# 07-TCXO_Crystal.net
KiCad netlist of a schematic drawn in Altium Designer
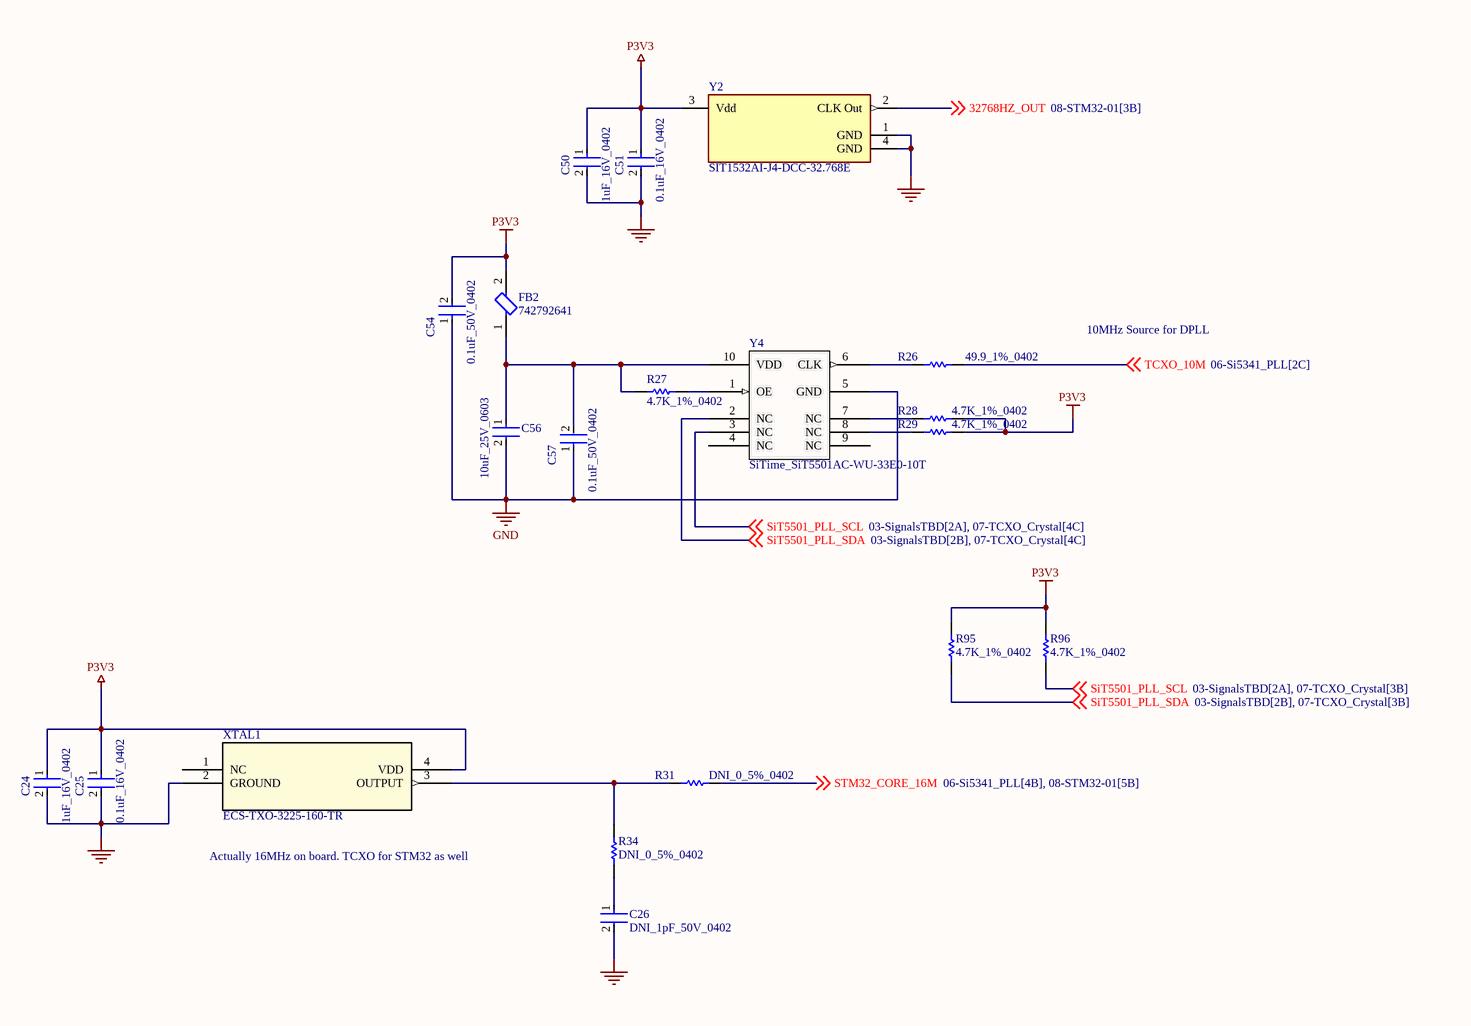
[diagram p0: 07-TCXO_Crystal.SchDoc]

(export (version "E")
  (design (tool "Eeschema 10.0.6"))
  (components
    (comp (ref "C24")
      (value "1uF_16V_0402")
      (footprint "FP-0402-L_1_0_0_05-W_0_5-IPC_A")
      (description "None")
      (fields (field (name "TOLERANCE") "10%"))
      (libsource (lib "Altium Content Vault") (part "b4654b650e69147ec39a6b967a45e02"))
    )
    (comp (ref "C25")
      (value "0.1uF_16V_0402")
      (footprint "FP-C0402-BB-MFG")
      (description "CAP CER 0.1UF 16V 5% X7R 0402")
      (fields
        (field (name "MANUFACTURER") "Kemet")
        (field (name "MANUFACTURER PART NUMBER") "C0402C104J4RACTU")
      )
      (libsource (lib "Altium Content Vault") (part "b4654b650e69147ec39a6b967a45e02"))
    )
    (comp (ref "C26")
      (value "DNI_1pF_50V_0402")
      (footprint "FP-GJM155-0_05-IPC_B")
      (description "Multi-Layer Ceramic Capacitor 1pF C0G  ±0.1pF 0402 Paper T/R")
      (fields (field (name "VOLTAGE") "50V"))
      (libsource (lib "Altium Content Vault") (part "02cd4be3c70576c341d710602a673aa"))
    )
    (comp (ref "C50")
      (value "1uF_16V_0402")
      (footprint "FP-0402-L_1_0_0_05-W_0_5-IPC_A")
      (description "None")
      (fields (field (name "TOLERANCE") "10%"))
      (libsource (lib "Altium Content Vault") (part "b4654b650e69147ec39a6b967a45e02"))
    )
    (comp (ref "C51")
      (value "0.1uF_16V_0402")
      (footprint "FP-C0402-BB-MFG")
      (description "CAP CER 0.1UF 16V 5% X7R 0402")
      (fields
        (field (name "MANUFACTURER") "Kemet")
        (field (name "MANUFACTURER PART NUMBER") "C0402C104J4RACTU")
      )
      (libsource (lib "Altium Content Vault") (part "b4654b650e69147ec39a6b967a45e02"))
    )
    (comp (ref "C54")
      (value "0.1uF_50V_0402")
      (footprint "FP-C1005-050-0_05-IPC_C")
      (description "Multilayer Ceramic Capacitors 100nF ±10% 50V X7R SMD 0402")
      (fields (field (name "VOLTAGE") "50V") (field (name "TOLERANCE") "10%"))
      (libsource (lib "Altium Content Vault") (part "b4654b650e69147ec39a6b967a45e02"))
    )
    (comp (ref "C56")
      (value "10uF_25V_0603")
      (footprint "FP-CL10-IPC_C")
      (description "Cap Ceramic 10uF 25V X5R ±20% Pad SMD 0603 +85°C T/R")
      (fields (field (name "TOLERANCE") "20%"))
      (libsource (lib "Altium Content Vault") (part "b4654b650e69147ec39a6b967a45e02"))
    )
    (comp (ref "C57")
      (value "0.1uF_50V_0402")
      (footprint "FP-C1005-050-0_05-IPC_C")
      (description "Multilayer Ceramic Capacitors 100nF ±10% 50V X7R SMD 0402")
      (fields (field (name "VOLTAGE") "50V") (field (name "TOLERANCE") "10%"))
      (libsource (lib "Altium Content Vault") (part "b4654b650e69147ec39a6b967a45e02"))
    )
    (comp (ref "FB2")
      (value "742792641")
      (footprint "FP-742792641-MFG")
      (description "FERRITE BEAD 300 OHM 0603 1LN")
      (fields (field (name "TOLERANCE") "25%"))
      (libsource (lib "Altium Content Vault") (part "5f30dd21d616792df468990f7003faa"))
    )
    (comp (ref "R26")
      (value "49.9_1%_0402")
      (footprint "RESC1005X40X25NL10T10")
      (fields (field (name "PART NUMBER") "RK73H1ETTP49R9F") (field (name "MANUFACTURER") "KOA Speer"))
      (libsource (lib "Altium Content Vault") (part "RES"))
    )
    (comp (ref "R27")
      (value "4.7K_1%_0402")
      (footprint "RESC1005X40X25NL10T10")
      (fields (field (name "MANUFACTURER") "Bourns") (field (name "PART NUMBER") "CR0402-FX-4701GLF"))
      (libsource (lib "Altium Content Vault") (part "RES"))
    )
    (comp (ref "R28")
      (value "4.7K_1%_0402")
      (footprint "RESC1005X40X25NL10T10")
      (fields (field (name "MANUFACTURER") "Bourns") (field (name "PART NUMBER") "CR0402-FX-4701GLF"))
      (libsource (lib "Altium Content Vault") (part "RES"))
    )
    (comp (ref "R29")
      (value "4.7K_1%_0402")
      (footprint "RESC1005X40X25NL10T10")
      (fields (field (name "MANUFACTURER") "Bourns") (field (name "PART NUMBER") "CR0402-FX-4701GLF"))
      (libsource (lib "Altium Content Vault") (part "RES"))
    )
    (comp (ref "R31")
      (value "DNI_0_5%_0402")
      (footprint "RESC1005X40X25NL05T10")
      (fields (field (name "MANUFACTURER") "Panasonic") (field (name "PART NUMBER") "ERJ-U020R00X"))
      (libsource (lib "Altium Content Vault") (part "RES"))
    )
    (comp (ref "R34")
      (value "DNI_0_5%_0402")
      (footprint "RESC1005X40X25NL05T10")
      (fields (field (name "MANUFACTURER") "Panasonic") (field (name "PART NUMBER") "ERJ-U020R00X"))
      (libsource (lib "Altium Content Vault") (part "RES"))
    )
    (comp (ref "R95")
      (value "4.7K_1%_0402")
      (footprint "RESC1005X40X25NL10T10")
      (fields (field (name "MANUFACTURER") "Bourns") (field (name "PART NUMBER") "CR0402-FX-4701GLF"))
      (libsource (lib "Altium Content Vault") (part "RES"))
    )
    (comp (ref "R96")
      (value "4.7K_1%_0402")
      (footprint "RESC1005X40X25NL10T10")
      (fields (field (name "MANUFACTURER") "Bourns") (field (name "PART NUMBER") "CR0402-FX-4701GLF"))
      (libsource (lib "Altium Content Vault") (part "RES"))
    )
    (comp (ref "XTAL1")
      (value "ECS-TXO-3225-160-TR")
      (footprint "ECS-TXO-3225_ECS")
      (description "No Description Available")
      (libsource (lib "ECS-TXO-3225-122P8-TR") (part "ECS-TXO-3225-122.8-TR"))
    )
    (comp (ref "Y2")
      (value "SIT1532AI-J4-DCC-32.768E")
      (footprint "FP-SIT1532-MFG")
      (description "MEMS OSC XO 32.7680KHZ LVCMOS")
      (libsource (lib "Altium Content Vault") (part "c4f9b1365e25d15033dfe34c89f26e6"))
    )
    (comp (ref "Y4")
      (value "SiTime_SiT5501AC-WU-33E0-10T")
      (footprint "SITIME_SPL-086-CQFN-010-C07050_REV_DRAFT")
      (description "OSC, MEMS, STRATUM 3E, 10.000MHZ, 10PPB STAB, LVCMOS, 3.3V, O/P EN, 7.0X5.0X2.2MM, CQFN-10")
      (fields
        (field (name "MANUFACTURER PART NUMBER") "SiT5501AI-WU033JH-10.000000")
        (field (name "MANUFACTURER") "SiTime")
      )
      (libsource (lib "OCXO_DaughterCard") (part "CMP-OSC-00029-2"))
    )
  )
  (nets
    (net (code "1") (name "32768HZ_OUT") (class "Default")
      (node (ref "Y2") (pin "2") (pinfunction "CLK_Out_2") (pintype "output"))
    )
    (net (code "2") (name "GND") (class "Default")
      (node (ref "C24") (pin "2") (pinfunction "2_2") (pintype "passive"))
      (node (ref "C25") (pin "2") (pinfunction "2_2") (pintype "passive"))
      (node (ref "C26") (pin "2") (pinfunction "2_2") (pintype "passive"))
      (node (ref "C50") (pin "2") (pinfunction "2_2") (pintype "passive"))
      (node (ref "C51") (pin "2") (pinfunction "2_2") (pintype "passive"))
      (node (ref "C54") (pin "1") (pinfunction "1_1") (pintype "passive"))
      (node (ref "C56") (pin "2") (pinfunction "2_2") (pintype "passive"))
      (node (ref "C57") (pin "1") (pinfunction "1_1") (pintype "passive"))
      (node (ref "XTAL1") (pin "2") (pinfunction "GROUND_2") (pintype "power_in"))
      (node (ref "Y2") (pin "1") (pinfunction "GND_1") (pintype "power_in"))
      (node (ref "Y2") (pin "4") (pinfunction "GND_4") (pintype "power_in"))
      (node (ref "Y4") (pin "5") (pinfunction "GND_5") (pintype "power_in"))
    )
    (net (code "3") (name "Net-(C26-Pad1)") (class "Default")
      (node (ref "C26") (pin "1") (pinfunction "1_1") (pintype "passive"))
      (node (ref "R34") (pin "1") (pinfunction "1_1") (pintype "passive"))
    )
    (net (code "4") (name "Net-(R28-Pad1)") (class "Default")
      (node (ref "R28") (pin "1") (pinfunction "1_1") (pintype "passive"))
      (node (ref "Y4") (pin "7") (pinfunction "NC_7") (pintype "passive"))
    )
    (net (code "5") (name "Net-(R29-Pad1)") (class "Default")
      (node (ref "R29") (pin "1") (pinfunction "1_1") (pintype "passive"))
      (node (ref "Y4") (pin "8") (pinfunction "NC_8") (pintype "passive"))
    )
    (net (code "6") (name "Net-(XTAL1-OUTPUT)") (class "Default")
      (node (ref "R31") (pin "1") (pinfunction "1_1") (pintype "passive"))
      (node (ref "R34") (pin "2") (pinfunction "2_2") (pintype "passive"))
      (node (ref "XTAL1") (pin "3") (pinfunction "OUTPUT_3") (pintype "output"))
    )
    (net (code "7") (name "Net-(Y4-CLK)") (class "Default")
      (node (ref "R26") (pin "2") (pinfunction "2_2") (pintype "passive"))
      (node (ref "Y4") (pin "6") (pinfunction "CLK_6") (pintype "output"))
    )
    (net (code "8") (name "Net-(Y4-OE)") (class "Default")
      (node (ref "R27") (pin "2") (pinfunction "2_2") (pintype "passive"))
      (node (ref "Y4") (pin "1") (pinfunction "OE_1") (pintype "input"))
    )
    (net (code "9") (name "Net-(Y4-VDD)") (class "Default")
      (node (ref "C56") (pin "1") (pinfunction "1_1") (pintype "passive"))
      (node (ref "C57") (pin "2") (pinfunction "2_2") (pintype "passive"))
      (node (ref "FB2") (pin "1") (pinfunction "1_1") (pintype "passive"))
      (node (ref "R27") (pin "1") (pinfunction "1_1") (pintype "passive"))
      (node (ref "Y4") (pin "10") (pinfunction "VDD_10") (pintype "power_in"))
    )
    (net (code "10") (name "P3V3") (class "Default")
      (node (ref "C24") (pin "1") (pinfunction "1_1") (pintype "passive"))
      (node (ref "C25") (pin "1") (pinfunction "1_1") (pintype "passive"))
      (node (ref "C50") (pin "1") (pinfunction "1_1") (pintype "passive"))
      (node (ref "C51") (pin "1") (pinfunction "1_1") (pintype "passive"))
      (node (ref "C54") (pin "2") (pinfunction "2_2") (pintype "passive"))
      (node (ref "FB2") (pin "2") (pinfunction "2_2") (pintype "passive"))
      (node (ref "R28") (pin "2") (pinfunction "2_2") (pintype "passive"))
      (node (ref "R29") (pin "2") (pinfunction "2_2") (pintype "passive"))
      (node (ref "R95") (pin "2") (pinfunction "2_2") (pintype "passive"))
      (node (ref "R96") (pin "2") (pinfunction "2_2") (pintype "passive"))
      (node (ref "XTAL1") (pin "4") (pinfunction "VDD_4") (pintype "power_in"))
      (node (ref "Y2") (pin "3") (pinfunction "Vdd_3") (pintype "power_in"))
    )
    (net (code "11") (name "STM32_CORE_16M") (class "Default")
      (node (ref "R31") (pin "2") (pinfunction "2_2") (pintype "passive"))
    )
    (net (code "12") (name "SiT5501_PLL_SCL") (class "Default")
      (node (ref "R96") (pin "1") (pinfunction "1_1") (pintype "passive"))
      (node (ref "Y4") (pin "3") (pinfunction "NC_3") (pintype "passive"))
    )
    (net (code "13") (name "SiT5501_PLL_SDA") (class "Default")
      (node (ref "R95") (pin "1") (pinfunction "1_1") (pintype "passive"))
      (node (ref "Y4") (pin "2") (pinfunction "NC_2") (pintype "passive"))
    )
    (net (code "14") (name "TCXO_10M") (class "Default")
      (node (ref "R26") (pin "1") (pinfunction "1_1") (pintype "passive"))
    )
    (net (code "15") (name "unconnected-(XTAL1-NC-Pad1)") (class "Default")
      (node (ref "XTAL1") (pin "1") (pinfunction "NC_1") (pintype "passive"))
    )
    (net (code "16") (name "unconnected-(Y4-NC-Pad4)") (class "Default")
      (node (ref "Y4") (pin "4") (pinfunction "NC_4") (pintype "passive"))
    )
    (net (code "17") (name "unconnected-(Y4-NC-Pad9)") (class "Default")
      (node (ref "Y4") (pin "9") (pinfunction "NC_9") (pintype "passive"))
    )
  )
)
